# Display.net
KiCad netlist of a schematic drawn in Altium Designer
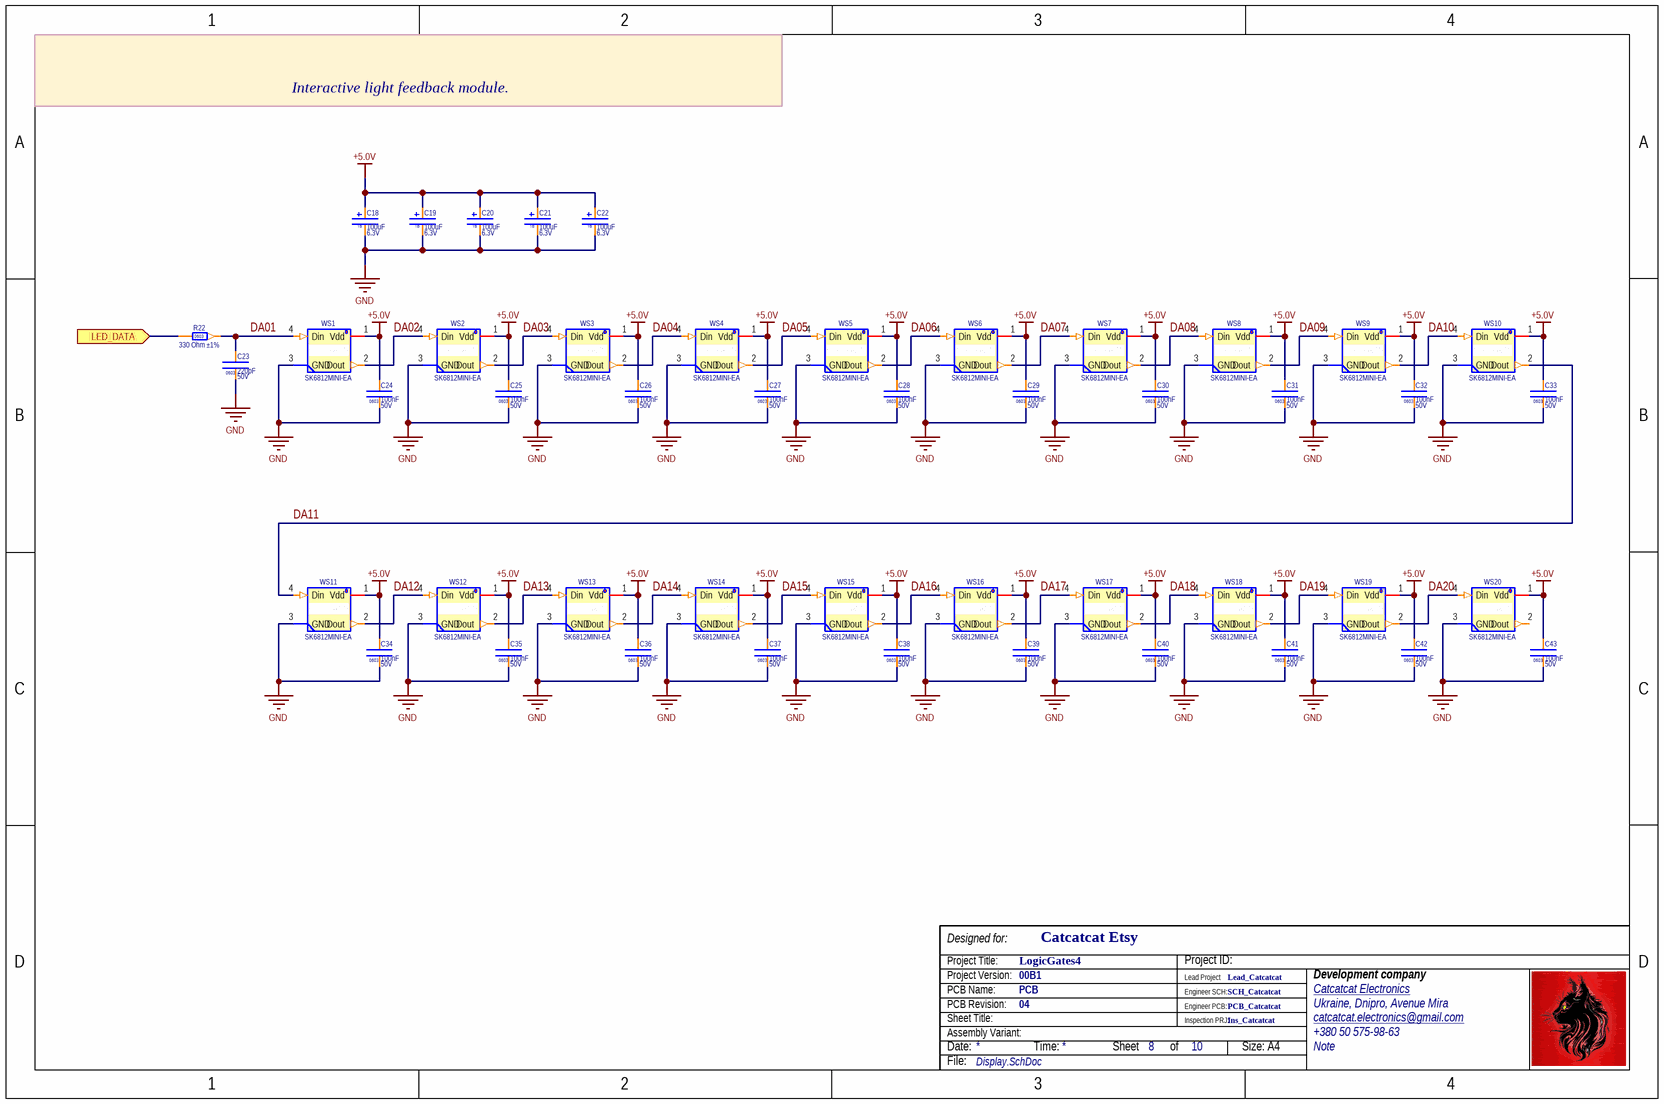
[diagram p0: Display.SchDoc]

(export (version "E")
  (design (tool "Eeschema 10.0.6"))
  (components
    (comp (ref "C18")
      (value "100uF")
      (footprint "TANTAL_B")
      (description "Tantalum Capacitors 100uF 6.3V CASE-B_3528 RoHS")
      (fields
        (field (name "VOLTAGE") "6.3V")
        (field (name "Comment") "100UF 6.3V CASE-B_3528")
        (field (name "PUBLISHER") "Catcatcat Electronics")
      )
      (libsource (lib "CapacitorElectrolytic") (part "TANTAL-B 100uF 6.3V (B)"))
    )
    (comp (ref "C19")
      (value "100uF")
      (footprint "TANTAL_B")
      (description "Tantalum Capacitors 100uF 6.3V CASE-B_3528 RoHS")
      (fields
        (field (name "VOLTAGE") "6.3V")
        (field (name "Comment") "100UF 6.3V CASE-B_3528")
        (field (name "PUBLISHER") "Catcatcat Electronics")
      )
      (libsource (lib "CapacitorElectrolytic") (part "TANTAL-B 100uF 6.3V (B)"))
    )
    (comp (ref "C20")
      (value "100uF")
      (footprint "TANTAL_B")
      (description "Tantalum Capacitors 100uF 6.3V CASE-B_3528 RoHS")
      (fields
        (field (name "VOLTAGE") "6.3V")
        (field (name "Comment") "100UF 6.3V CASE-B_3528")
        (field (name "PUBLISHER") "Catcatcat Electronics")
      )
      (libsource (lib "CapacitorElectrolytic") (part "TANTAL-B 100uF 6.3V (B)"))
    )
    (comp (ref "C21")
      (value "100uF")
      (footprint "TANTAL_B")
      (description "Tantalum Capacitors 100uF 6.3V CASE-B_3528 RoHS")
      (fields
        (field (name "VOLTAGE") "6.3V")
        (field (name "Comment") "100UF 6.3V CASE-B_3528")
        (field (name "PUBLISHER") "Catcatcat Electronics")
      )
      (libsource (lib "CapacitorElectrolytic") (part "TANTAL-B 100uF 6.3V (B)"))
    )
    (comp (ref "C22")
      (value "100uF")
      (footprint "TANTAL_B")
      (description "Tantalum Capacitors 100uF 6.3V CASE-B_3528 RoHS")
      (fields
        (field (name "VOLTAGE") "6.3V")
        (field (name "Comment") "100UF 6.3V CASE-B_3528")
        (field (name "PUBLISHER") "Catcatcat Electronics")
      )
      (libsource (lib "CapacitorElectrolytic") (part "TANTAL-B 100uF 6.3V (B)"))
    )
    (comp (ref "C23")
      (value "220pF")
      (footprint "CC0603(1608)x0.8")
      (description "220 pF ±10% 50V X7R")
      (fields
        (field (name "TOLERANCE") "±10%")
        (field (name "VOLTAGE") "50V")
        (field (name "Comment") "220 pF ±10%")
        (field (name "PUBLISHER") "Catcatcat Electronics")
      )
      (libsource (lib "IPC-7351chipCAPC") (part "0603 0.000220 uF (B)"))
    )
    (comp (ref "C24")
      (value "100nF")
      (footprint "CC0603(1608)x0.8")
      (description "100 nF ±10% 50V X7R")
      (fields
        (field (name "TOLERANCE") "±10%")
        (field (name "VOLTAGE") "50V")
        (field (name "Comment") "100 nF ±10% 50V")
        (field (name "PUBLISHER") "Catcatcat Electronics")
      )
      (libsource (lib "IPC-7351chipCAPC") (part "0603 0.1 uF (B)"))
    )
    (comp (ref "C25")
      (value "100nF")
      (footprint "CC0603(1608)x0.8")
      (description "100 nF ±10% 50V X7R")
      (fields
        (field (name "TOLERANCE") "±10%")
        (field (name "VOLTAGE") "50V")
        (field (name "Comment") "100 nF ±10% 50V")
        (field (name "PUBLISHER") "Catcatcat Electronics")
      )
      (libsource (lib "IPC-7351chipCAPC") (part "0603 0.1 uF (B)"))
    )
    (comp (ref "C26")
      (value "100nF")
      (footprint "CC0603(1608)x0.8")
      (description "100 nF ±10% 50V X7R")
      (fields
        (field (name "TOLERANCE") "±10%")
        (field (name "VOLTAGE") "50V")
        (field (name "Comment") "100 nF ±10% 50V")
        (field (name "PUBLISHER") "Catcatcat Electronics")
      )
      (libsource (lib "IPC-7351chipCAPC") (part "0603 0.1 uF (B)"))
    )
    (comp (ref "C27")
      (value "100nF")
      (footprint "CC0603(1608)x0.8")
      (description "100 nF ±10% 50V X7R")
      (fields
        (field (name "TOLERANCE") "±10%")
        (field (name "VOLTAGE") "50V")
        (field (name "Comment") "100 nF ±10% 50V")
        (field (name "PUBLISHER") "Catcatcat Electronics")
      )
      (libsource (lib "IPC-7351chipCAPC") (part "0603 0.1 uF (B)"))
    )
    (comp (ref "C28")
      (value "100nF")
      (footprint "CC0603(1608)x0.8")
      (description "100 nF ±10% 50V X7R")
      (fields
        (field (name "TOLERANCE") "±10%")
        (field (name "VOLTAGE") "50V")
        (field (name "Comment") "100 nF ±10% 50V")
        (field (name "PUBLISHER") "Catcatcat Electronics")
      )
      (libsource (lib "IPC-7351chipCAPC") (part "0603 0.1 uF (B)"))
    )
    (comp (ref "C29")
      (value "100nF")
      (footprint "CC0603(1608)x0.8")
      (description "100 nF ±10% 50V X7R")
      (fields
        (field (name "TOLERANCE") "±10%")
        (field (name "VOLTAGE") "50V")
        (field (name "Comment") "100 nF ±10% 50V")
        (field (name "PUBLISHER") "Catcatcat Electronics")
      )
      (libsource (lib "IPC-7351chipCAPC") (part "0603 0.1 uF (B)"))
    )
    (comp (ref "C30")
      (value "100nF")
      (footprint "CC0603(1608)x0.8")
      (description "100 nF ±10% 50V X7R")
      (fields
        (field (name "TOLERANCE") "±10%")
        (field (name "VOLTAGE") "50V")
        (field (name "Comment") "100 nF ±10% 50V")
        (field (name "PUBLISHER") "Catcatcat Electronics")
      )
      (libsource (lib "IPC-7351chipCAPC") (part "0603 0.1 uF (B)"))
    )
    (comp (ref "C31")
      (value "100nF")
      (footprint "CC0603(1608)x0.8")
      (description "100 nF ±10% 50V X7R")
      (fields
        (field (name "TOLERANCE") "±10%")
        (field (name "VOLTAGE") "50V")
        (field (name "Comment") "100 nF ±10% 50V")
        (field (name "PUBLISHER") "Catcatcat Electronics")
      )
      (libsource (lib "IPC-7351chipCAPC") (part "0603 0.1 uF (B)"))
    )
    (comp (ref "C32")
      (value "100nF")
      (footprint "CC0603(1608)x0.8")
      (description "100 nF ±10% 50V X7R")
      (fields
        (field (name "TOLERANCE") "±10%")
        (field (name "VOLTAGE") "50V")
        (field (name "Comment") "100 nF ±10% 50V")
        (field (name "PUBLISHER") "Catcatcat Electronics")
      )
      (libsource (lib "IPC-7351chipCAPC") (part "0603 0.1 uF (B)"))
    )
    (comp (ref "C33")
      (value "100nF")
      (footprint "CC0603(1608)x0.8")
      (description "100 nF ±10% 50V X7R")
      (fields
        (field (name "TOLERANCE") "±10%")
        (field (name "VOLTAGE") "50V")
        (field (name "Comment") "100 nF ±10% 50V")
        (field (name "PUBLISHER") "Catcatcat Electronics")
      )
      (libsource (lib "IPC-7351chipCAPC") (part "0603 0.1 uF (B)"))
    )
    (comp (ref "C34")
      (value "100nF")
      (footprint "CC0603(1608)x0.8")
      (description "100 nF ±10% 50V X7R")
      (fields
        (field (name "TOLERANCE") "±10%")
        (field (name "VOLTAGE") "50V")
        (field (name "Comment") "100 nF ±10% 50V")
        (field (name "PUBLISHER") "Catcatcat Electronics")
      )
      (libsource (lib "IPC-7351chipCAPC") (part "0603 0.1 uF (B)"))
    )
    (comp (ref "C35")
      (value "100nF")
      (footprint "CC0603(1608)x0.8")
      (description "100 nF ±10% 50V X7R")
      (fields
        (field (name "TOLERANCE") "±10%")
        (field (name "VOLTAGE") "50V")
        (field (name "Comment") "100 nF ±10% 50V")
        (field (name "PUBLISHER") "Catcatcat Electronics")
      )
      (libsource (lib "IPC-7351chipCAPC") (part "0603 0.1 uF (B)"))
    )
    (comp (ref "C36")
      (value "100nF")
      (footprint "CC0603(1608)x0.8")
      (description "100 nF ±10% 50V X7R")
      (fields
        (field (name "TOLERANCE") "±10%")
        (field (name "VOLTAGE") "50V")
        (field (name "Comment") "100 nF ±10% 50V")
        (field (name "PUBLISHER") "Catcatcat Electronics")
      )
      (libsource (lib "IPC-7351chipCAPC") (part "0603 0.1 uF (B)"))
    )
    (comp (ref "C37")
      (value "100nF")
      (footprint "CC0603(1608)x0.8")
      (description "100 nF ±10% 50V X7R")
      (fields
        (field (name "TOLERANCE") "±10%")
        (field (name "VOLTAGE") "50V")
        (field (name "Comment") "100 nF ±10% 50V")
        (field (name "PUBLISHER") "Catcatcat Electronics")
      )
      (libsource (lib "IPC-7351chipCAPC") (part "0603 0.1 uF (B)"))
    )
    (comp (ref "C38")
      (value "100nF")
      (footprint "CC0603(1608)x0.8")
      (description "100 nF ±10% 50V X7R")
      (fields
        (field (name "TOLERANCE") "±10%")
        (field (name "VOLTAGE") "50V")
        (field (name "Comment") "100 nF ±10% 50V")
        (field (name "PUBLISHER") "Catcatcat Electronics")
      )
      (libsource (lib "IPC-7351chipCAPC") (part "0603 0.1 uF (B)"))
    )
    (comp (ref "C39")
      (value "100nF")
      (footprint "CC0603(1608)x0.8")
      (description "100 nF ±10% 50V X7R")
      (fields
        (field (name "TOLERANCE") "±10%")
        (field (name "VOLTAGE") "50V")
        (field (name "Comment") "100 nF ±10% 50V")
        (field (name "PUBLISHER") "Catcatcat Electronics")
      )
      (libsource (lib "IPC-7351chipCAPC") (part "0603 0.1 uF (B)"))
    )
    (comp (ref "C40")
      (value "100nF")
      (footprint "CC0603(1608)x0.8")
      (description "100 nF ±10% 50V X7R")
      (fields
        (field (name "TOLERANCE") "±10%")
        (field (name "VOLTAGE") "50V")
        (field (name "Comment") "100 nF ±10% 50V")
        (field (name "PUBLISHER") "Catcatcat Electronics")
      )
      (libsource (lib "IPC-7351chipCAPC") (part "0603 0.1 uF (B)"))
    )
    (comp (ref "C41")
      (value "100nF")
      (footprint "CC0603(1608)x0.8")
      (description "100 nF ±10% 50V X7R")
      (fields
        (field (name "TOLERANCE") "±10%")
        (field (name "VOLTAGE") "50V")
        (field (name "Comment") "100 nF ±10% 50V")
        (field (name "PUBLISHER") "Catcatcat Electronics")
      )
      (libsource (lib "IPC-7351chipCAPC") (part "0603 0.1 uF (B)"))
    )
    (comp (ref "C42")
      (value "100nF")
      (footprint "CC0603(1608)x0.8")
      (description "100 nF ±10% 50V X7R")
      (fields
        (field (name "TOLERANCE") "±10%")
        (field (name "VOLTAGE") "50V")
        (field (name "Comment") "100 nF ±10% 50V")
        (field (name "PUBLISHER") "Catcatcat Electronics")
      )
      (libsource (lib "IPC-7351chipCAPC") (part "0603 0.1 uF (B)"))
    )
    (comp (ref "C43")
      (value "100nF")
      (footprint "CC0603(1608)x0.8")
      (description "100 nF ±10% 50V X7R")
      (fields
        (field (name "TOLERANCE") "±10%")
        (field (name "VOLTAGE") "50V")
        (field (name "Comment") "100 nF ±10% 50V")
        (field (name "PUBLISHER") "Catcatcat Electronics")
      )
      (libsource (lib "IPC-7351chipCAPC") (part "0603 0.1 uF (B)"))
    )
    (comp (ref "R22")
      (value "330 Ohm ±1%")
      (footprint "RC0603(1608) -1%")
      (description "330 R (331) ±5% 1/10W 50V")
      (fields
        (field (name "TOLERANCE") "±1%")
        (field (name "VOLTAGE") "50V")
        (field (name "PUBLISHER") "Catcatcat Electronics")
      )
      (libsource (lib "IPC-7351chipRESC") (part "0603 330 Ohm ±1% (B)"))
    )
    (comp (ref "WS1")
      (value "SK6812MINI-EA")
      (footprint "SK6812MINI-EA - 1MM")
      (description "TTB 12mA 5.2V -40℃~+80℃ RGB LEDs(Built-in IC)")
      (fields (field (name "VOLTAGE") "+3.7~+5.3V") (field (name "PUBLISHER") "Catcatcat Electronics"))
      (libsource (lib "Led_chip") (part "SK6812MINI-EA (E)"))
    )
    (comp (ref "WS2")
      (value "SK6812MINI-EA")
      (footprint "SK6812MINI-EA - 1MM")
      (description "TTB 12mA 5.2V -40℃~+80℃ RGB LEDs(Built-in IC)")
      (fields (field (name "VOLTAGE") "+3.7~+5.3V") (field (name "PUBLISHER") "Catcatcat Electronics"))
      (libsource (lib "Led_chip") (part "SK6812MINI-EA (E)"))
    )
    (comp (ref "WS3")
      (value "SK6812MINI-EA")
      (footprint "SK6812MINI-EA - 1MM")
      (description "TTB 12mA 5.2V -40℃~+80℃ RGB LEDs(Built-in IC)")
      (fields (field (name "VOLTAGE") "+3.7~+5.3V") (field (name "PUBLISHER") "Catcatcat Electronics"))
      (libsource (lib "Led_chip") (part "SK6812MINI-EA (E)"))
    )
    (comp (ref "WS4")
      (value "SK6812MINI-EA")
      (footprint "SK6812MINI-EA - 1MM")
      (description "TTB 12mA 5.2V -40℃~+80℃ RGB LEDs(Built-in IC)")
      (fields (field (name "VOLTAGE") "+3.7~+5.3V") (field (name "PUBLISHER") "Catcatcat Electronics"))
      (libsource (lib "Led_chip") (part "SK6812MINI-EA (E)"))
    )
    (comp (ref "WS5")
      (value "SK6812MINI-EA")
      (footprint "SK6812MINI-EA - 1MM")
      (description "TTB 12mA 5.2V -40℃~+80℃ RGB LEDs(Built-in IC)")
      (fields (field (name "VOLTAGE") "+3.7~+5.3V") (field (name "PUBLISHER") "Catcatcat Electronics"))
      (libsource (lib "Led_chip") (part "SK6812MINI-EA (E)"))
    )
    (comp (ref "WS6")
      (value "SK6812MINI-EA")
      (footprint "SK6812MINI-EA - 1MM")
      (description "TTB 12mA 5.2V -40℃~+80℃ RGB LEDs(Built-in IC)")
      (fields (field (name "VOLTAGE") "+3.7~+5.3V") (field (name "PUBLISHER") "Catcatcat Electronics"))
      (libsource (lib "Led_chip") (part "SK6812MINI-EA (E)"))
    )
    (comp (ref "WS7")
      (value "SK6812MINI-EA")
      (footprint "SK6812MINI-EA - 1MM")
      (description "TTB 12mA 5.2V -40℃~+80℃ RGB LEDs(Built-in IC)")
      (fields (field (name "VOLTAGE") "+3.7~+5.3V") (field (name "PUBLISHER") "Catcatcat Electronics"))
      (libsource (lib "Led_chip") (part "SK6812MINI-EA (E)"))
    )
    (comp (ref "WS8")
      (value "SK6812MINI-EA")
      (footprint "SK6812MINI-EA - 1MM")
      (description "TTB 12mA 5.2V -40℃~+80℃ RGB LEDs(Built-in IC)")
      (fields (field (name "VOLTAGE") "+3.7~+5.3V") (field (name "PUBLISHER") "Catcatcat Electronics"))
      (libsource (lib "Led_chip") (part "SK6812MINI-EA (E)"))
    )
    (comp (ref "WS9")
      (value "SK6812MINI-EA")
      (footprint "SK6812MINI-EA - 1MM")
      (description "TTB 12mA 5.2V -40℃~+80℃ RGB LEDs(Built-in IC)")
      (fields (field (name "VOLTAGE") "+3.7~+5.3V") (field (name "PUBLISHER") "Catcatcat Electronics"))
      (libsource (lib "Led_chip") (part "SK6812MINI-EA (E)"))
    )
    (comp (ref "WS10")
      (value "SK6812MINI-EA")
      (footprint "SK6812MINI-EA - 1MM")
      (description "TTB 12mA 5.2V -40℃~+80℃ RGB LEDs(Built-in IC)")
      (fields (field (name "VOLTAGE") "+3.7~+5.3V") (field (name "PUBLISHER") "Catcatcat Electronics"))
      (libsource (lib "Led_chip") (part "SK6812MINI-EA (E)"))
    )
    (comp (ref "WS11")
      (value "SK6812MINI-EA")
      (footprint "SK6812MINI-EA - 1MM")
      (description "TTB 12mA 5.2V -40℃~+80℃ RGB LEDs(Built-in IC)")
      (fields (field (name "VOLTAGE") "+3.7~+5.3V") (field (name "PUBLISHER") "Catcatcat Electronics"))
      (libsource (lib "Led_chip") (part "SK6812MINI-EA (E)"))
    )
    (comp (ref "WS12")
      (value "SK6812MINI-EA")
      (footprint "SK6812MINI-EA - 1MM")
      (description "TTB 12mA 5.2V -40℃~+80℃ RGB LEDs(Built-in IC)")
      (fields (field (name "VOLTAGE") "+3.7~+5.3V") (field (name "PUBLISHER") "Catcatcat Electronics"))
      (libsource (lib "Led_chip") (part "SK6812MINI-EA (E)"))
    )
    (comp (ref "WS13")
      (value "SK6812MINI-EA")
      (footprint "SK6812MINI-EA - 1MM")
      (description "TTB 12mA 5.2V -40℃~+80℃ RGB LEDs(Built-in IC)")
      (fields (field (name "VOLTAGE") "+3.7~+5.3V") (field (name "PUBLISHER") "Catcatcat Electronics"))
      (libsource (lib "Led_chip") (part "SK6812MINI-EA (E)"))
    )
    (comp (ref "WS14")
      (value "SK6812MINI-EA")
      (footprint "SK6812MINI-EA - 1MM")
      (description "TTB 12mA 5.2V -40℃~+80℃ RGB LEDs(Built-in IC)")
      (fields (field (name "VOLTAGE") "+3.7~+5.3V") (field (name "PUBLISHER") "Catcatcat Electronics"))
      (libsource (lib "Led_chip") (part "SK6812MINI-EA (E)"))
    )
    (comp (ref "WS15")
      (value "SK6812MINI-EA")
      (footprint "SK6812MINI-EA - 1MM")
      (description "TTB 12mA 5.2V -40℃~+80℃ RGB LEDs(Built-in IC)")
      (fields (field (name "VOLTAGE") "+3.7~+5.3V") (field (name "PUBLISHER") "Catcatcat Electronics"))
      (libsource (lib "Led_chip") (part "SK6812MINI-EA (E)"))
    )
    (comp (ref "WS16")
      (value "SK6812MINI-EA")
      (footprint "SK6812MINI-EA - 1MM")
      (description "TTB 12mA 5.2V -40℃~+80℃ RGB LEDs(Built-in IC)")
      (fields (field (name "VOLTAGE") "+3.7~+5.3V") (field (name "PUBLISHER") "Catcatcat Electronics"))
      (libsource (lib "Led_chip") (part "SK6812MINI-EA (E)"))
    )
    (comp (ref "WS17")
      (value "SK6812MINI-EA")
      (footprint "SK6812MINI-EA - 1MM")
      (description "TTB 12mA 5.2V -40℃~+80℃ RGB LEDs(Built-in IC)")
      (fields (field (name "VOLTAGE") "+3.7~+5.3V") (field (name "PUBLISHER") "Catcatcat Electronics"))
      (libsource (lib "Led_chip") (part "SK6812MINI-EA (E)"))
    )
    (comp (ref "WS18")
      (value "SK6812MINI-EA")
      (footprint "SK6812MINI-EA - 1MM")
      (description "TTB 12mA 5.2V -40℃~+80℃ RGB LEDs(Built-in IC)")
      (fields (field (name "VOLTAGE") "+3.7~+5.3V") (field (name "PUBLISHER") "Catcatcat Electronics"))
      (libsource (lib "Led_chip") (part "SK6812MINI-EA (E)"))
    )
    (comp (ref "WS19")
      (value "SK6812MINI-EA")
      (footprint "SK6812MINI-EA - 1MM")
      (description "TTB 12mA 5.2V -40℃~+80℃ RGB LEDs(Built-in IC)")
      (fields (field (name "VOLTAGE") "+3.7~+5.3V") (field (name "PUBLISHER") "Catcatcat Electronics"))
      (libsource (lib "Led_chip") (part "SK6812MINI-EA (E)"))
    )
    (comp (ref "WS20")
      (value "SK6812MINI-EA")
      (footprint "SK6812MINI-EA - 1MM")
      (description "TTB 12mA 5.2V -40℃~+80℃ RGB LEDs(Built-in IC)")
      (fields (field (name "VOLTAGE") "+3.7~+5.3V") (field (name "PUBLISHER") "Catcatcat Electronics"))
      (libsource (lib "Led_chip") (part "SK6812MINI-EA (E)"))
    )
  )
  (nets
    (net (code "1") (name "+5.0V") (class "Default")
      (node (ref "C18") (pin "1") (pintype "passive"))
      (node (ref "C19") (pin "1") (pintype "passive"))
      (node (ref "C20") (pin "1") (pintype "passive"))
      (node (ref "C21") (pin "1") (pintype "passive"))
      (node (ref "C22") (pin "1") (pintype "passive"))
      (node (ref "C24") (pin "2") (pintype "passive"))
      (node (ref "C25") (pin "2") (pintype "passive"))
      (node (ref "C26") (pin "2") (pintype "passive"))
      (node (ref "C27") (pin "2") (pintype "passive"))
      (node (ref "C28") (pin "2") (pintype "passive"))
      (node (ref "C29") (pin "2") (pintype "passive"))
      (node (ref "C30") (pin "2") (pintype "passive"))
      (node (ref "C31") (pin "2") (pintype "passive"))
      (node (ref "C32") (pin "2") (pintype "passive"))
      (node (ref "C33") (pin "2") (pintype "passive"))
      (node (ref "C34") (pin "2") (pintype "passive"))
      (node (ref "C35") (pin "2") (pintype "passive"))
      (node (ref "C36") (pin "2") (pintype "passive"))
      (node (ref "C37") (pin "2") (pintype "passive"))
      (node (ref "C38") (pin "2") (pintype "passive"))
      (node (ref "C39") (pin "2") (pintype "passive"))
      (node (ref "C40") (pin "2") (pintype "passive"))
      (node (ref "C41") (pin "2") (pintype "passive"))
      (node (ref "C42") (pin "2") (pintype "passive"))
      (node (ref "C43") (pin "2") (pintype "passive"))
      (node (ref "WS1") (pin "1") (pinfunction "Vdd_1") (pintype "passive"))
      (node (ref "WS10") (pin "1") (pinfunction "Vdd_1") (pintype "passive"))
      (node (ref "WS11") (pin "1") (pinfunction "Vdd_1") (pintype "passive"))
      (node (ref "WS12") (pin "1") (pinfunction "Vdd_1") (pintype "passive"))
      (node (ref "WS13") (pin "1") (pinfunction "Vdd_1") (pintype "passive"))
      (node (ref "WS14") (pin "1") (pinfunction "Vdd_1") (pintype "passive"))
      (node (ref "WS15") (pin "1") (pinfunction "Vdd_1") (pintype "passive"))
      (node (ref "WS16") (pin "1") (pinfunction "Vdd_1") (pintype "passive"))
      (node (ref "WS17") (pin "1") (pinfunction "Vdd_1") (pintype "passive"))
      (node (ref "WS18") (pin "1") (pinfunction "Vdd_1") (pintype "passive"))
      (node (ref "WS19") (pin "1") (pinfunction "Vdd_1") (pintype "passive"))
      (node (ref "WS2") (pin "1") (pinfunction "Vdd_1") (pintype "passive"))
      (node (ref "WS20") (pin "1") (pinfunction "Vdd_1") (pintype "passive"))
      (node (ref "WS3") (pin "1") (pinfunction "Vdd_1") (pintype "passive"))
      (node (ref "WS4") (pin "1") (pinfunction "Vdd_1") (pintype "passive"))
      (node (ref "WS5") (pin "1") (pinfunction "Vdd_1") (pintype "passive"))
      (node (ref "WS6") (pin "1") (pinfunction "Vdd_1") (pintype "passive"))
      (node (ref "WS7") (pin "1") (pinfunction "Vdd_1") (pintype "passive"))
      (node (ref "WS8") (pin "1") (pinfunction "Vdd_1") (pintype "passive"))
      (node (ref "WS9") (pin "1") (pinfunction "Vdd_1") (pintype "passive"))
    )
    (net (code "2") (name "/DA01") (class "Default")
      (node (ref "C23") (pin "2") (pintype "passive"))
      (node (ref "R22") (pin "2") (pintype "output"))
      (node (ref "WS1") (pin "4") (pinfunction "Din_4") (pintype "input"))
    )
    (net (code "3") (name "/DA02") (class "Default")
      (node (ref "WS1") (pin "2") (pinfunction "Dout_2") (pintype "output"))
      (node (ref "WS2") (pin "4") (pinfunction "Din_4") (pintype "input"))
    )
    (net (code "4") (name "/DA03") (class "Default")
      (node (ref "WS2") (pin "2") (pinfunction "Dout_2") (pintype "output"))
      (node (ref "WS3") (pin "4") (pinfunction "Din_4") (pintype "input"))
    )
    (net (code "5") (name "/DA04") (class "Default")
      (node (ref "WS3") (pin "2") (pinfunction "Dout_2") (pintype "output"))
      (node (ref "WS4") (pin "4") (pinfunction "Din_4") (pintype "input"))
    )
    (net (code "6") (name "/DA05") (class "Default")
      (node (ref "WS4") (pin "2") (pinfunction "Dout_2") (pintype "output"))
      (node (ref "WS5") (pin "4") (pinfunction "Din_4") (pintype "input"))
    )
    (net (code "7") (name "/DA06") (class "Default")
      (node (ref "WS5") (pin "2") (pinfunction "Dout_2") (pintype "output"))
      (node (ref "WS6") (pin "4") (pinfunction "Din_4") (pintype "input"))
    )
    (net (code "8") (name "/DA07") (class "Default")
      (node (ref "WS6") (pin "2") (pinfunction "Dout_2") (pintype "output"))
      (node (ref "WS7") (pin "4") (pinfunction "Din_4") (pintype "input"))
    )
    (net (code "9") (name "/DA08") (class "Default")
      (node (ref "WS7") (pin "2") (pinfunction "Dout_2") (pintype "output"))
      (node (ref "WS8") (pin "4") (pinfunction "Din_4") (pintype "input"))
    )
    (net (code "10") (name "/DA09") (class "Default")
      (node (ref "WS8") (pin "2") (pinfunction "Dout_2") (pintype "output"))
      (node (ref "WS9") (pin "4") (pinfunction "Din_4") (pintype "input"))
    )
    (net (code "11") (name "/DA10") (class "Default")
      (node (ref "WS10") (pin "4") (pinfunction "Din_4") (pintype "input"))
      (node (ref "WS9") (pin "2") (pinfunction "Dout_2") (pintype "output"))
    )
    (net (code "12") (name "/DA11") (class "Default")
      (node (ref "WS10") (pin "2") (pinfunction "Dout_2") (pintype "output"))
      (node (ref "WS11") (pin "4") (pinfunction "Din_4") (pintype "input"))
    )
    (net (code "13") (name "/DA12") (class "Default")
      (node (ref "WS11") (pin "2") (pinfunction "Dout_2") (pintype "output"))
      (node (ref "WS12") (pin "4") (pinfunction "Din_4") (pintype "input"))
    )
    (net (code "14") (name "/DA13") (class "Default")
      (node (ref "WS12") (pin "2") (pinfunction "Dout_2") (pintype "output"))
      (node (ref "WS13") (pin "4") (pinfunction "Din_4") (pintype "input"))
    )
    (net (code "15") (name "/DA14") (class "Default")
      (node (ref "WS13") (pin "2") (pinfunction "Dout_2") (pintype "output"))
      (node (ref "WS14") (pin "4") (pinfunction "Din_4") (pintype "input"))
    )
    (net (code "16") (name "/DA15") (class "Default")
      (node (ref "WS14") (pin "2") (pinfunction "Dout_2") (pintype "output"))
      (node (ref "WS15") (pin "4") (pinfunction "Din_4") (pintype "input"))
    )
    (net (code "17") (name "/DA16") (class "Default")
      (node (ref "WS15") (pin "2") (pinfunction "Dout_2") (pintype "output"))
      (node (ref "WS16") (pin "4") (pinfunction "Din_4") (pintype "input"))
    )
    (net (code "18") (name "/DA17") (class "Default")
      (node (ref "WS16") (pin "2") (pinfunction "Dout_2") (pintype "output"))
      (node (ref "WS17") (pin "4") (pinfunction "Din_4") (pintype "input"))
    )
    (net (code "19") (name "/DA18") (class "Default")
      (node (ref "WS17") (pin "2") (pinfunction "Dout_2") (pintype "output"))
      (node (ref "WS18") (pin "4") (pinfunction "Din_4") (pintype "input"))
    )
    (net (code "20") (name "/DA19") (class "Default")
      (node (ref "WS18") (pin "2") (pinfunction "Dout_2") (pintype "output"))
      (node (ref "WS19") (pin "4") (pinfunction "Din_4") (pintype "input"))
    )
    (net (code "21") (name "/DA20") (class "Default")
      (node (ref "WS19") (pin "2") (pinfunction "Dout_2") (pintype "output"))
      (node (ref "WS20") (pin "4") (pinfunction "Din_4") (pintype "input"))
    )
    (net (code "22") (name "/LED_DATA") (class "Default") (node (ref "R22") (pin "1") (pintype "passive")))
    (net (code "23") (name "GND") (class "Default")
      (node (ref "C18") (pin "2") (pintype "passive"))
      (node (ref "C19") (pin "2") (pintype "passive"))
      (node (ref "C20") (pin "2") (pintype "passive"))
      (node (ref "C21") (pin "2") (pintype "passive"))
      (node (ref "C22") (pin "2") (pintype "passive"))
      (node (ref "C23") (pin "1") (pintype "passive"))
      (node (ref "C24") (pin "1") (pintype "passive"))
      (node (ref "C25") (pin "1") (pintype "passive"))
      (node (ref "C26") (pin "1") (pintype "passive"))
      (node (ref "C27") (pin "1") (pintype "passive"))
      (node (ref "C28") (pin "1") (pintype "passive"))
      (node (ref "C29") (pin "1") (pintype "passive"))
      (node (ref "C30") (pin "1") (pintype "passive"))
      (node (ref "C31") (pin "1") (pintype "passive"))
      (node (ref "C32") (pin "1") (pintype "passive"))
      (node (ref "C33") (pin "1") (pintype "passive"))
      (node (ref "C34") (pin "1") (pintype "passive"))
      (node (ref "C35") (pin "1") (pintype "passive"))
      (node (ref "C36") (pin "1") (pintype "passive"))
      (node (ref "C37") (pin "1") (pintype "passive"))
      (node (ref "C38") (pin "1") (pintype "passive"))
      (node (ref "C39") (pin "1") (pintype "passive"))
      (node (ref "C40") (pin "1") (pintype "passive"))
      (node (ref "C41") (pin "1") (pintype "passive"))
      (node (ref "C42") (pin "1") (pintype "passive"))
      (node (ref "C43") (pin "1") (pintype "passive"))
      (node (ref "WS1") (pin "3") (pinfunction "GND_3") (pintype "passive"))
      (node (ref "WS10") (pin "3") (pinfunction "GND_3") (pintype "passive"))
      (node (ref "WS11") (pin "3") (pinfunction "GND_3") (pintype "passive"))
      (node (ref "WS12") (pin "3") (pinfunction "GND_3") (pintype "passive"))
      (node (ref "WS13") (pin "3") (pinfunction "GND_3") (pintype "passive"))
      (node (ref "WS14") (pin "3") (pinfunction "GND_3") (pintype "passive"))
      (node (ref "WS15") (pin "3") (pinfunction "GND_3") (pintype "passive"))
      (node (ref "WS16") (pin "3") (pinfunction "GND_3") (pintype "passive"))
      (node (ref "WS17") (pin "3") (pinfunction "GND_3") (pintype "passive"))
      (node (ref "WS18") (pin "3") (pinfunction "GND_3") (pintype "passive"))
      (node (ref "WS19") (pin "3") (pinfunction "GND_3") (pintype "passive"))
      (node (ref "WS2") (pin "3") (pinfunction "GND_3") (pintype "passive"))
      (node (ref "WS20") (pin "3") (pinfunction "GND_3") (pintype "passive"))
      (node (ref "WS3") (pin "3") (pinfunction "GND_3") (pintype "passive"))
      (node (ref "WS4") (pin "3") (pinfunction "GND_3") (pintype "passive"))
      (node (ref "WS5") (pin "3") (pinfunction "GND_3") (pintype "passive"))
      (node (ref "WS6") (pin "3") (pinfunction "GND_3") (pintype "passive"))
      (node (ref "WS7") (pin "3") (pinfunction "GND_3") (pintype "passive"))
      (node (ref "WS8") (pin "3") (pinfunction "GND_3") (pintype "passive"))
      (node (ref "WS9") (pin "3") (pinfunction "GND_3") (pintype "passive"))
    )
    (net (code "24") (name "unconnected-(WS20-Dout-Pad2)") (class "Default")
      (node (ref "WS20") (pin "2") (pinfunction "Dout_2") (pintype "output"))
    )
  )
)
